# chaprshield.net
KiCad netlist of a schematic drawn in EAGLE
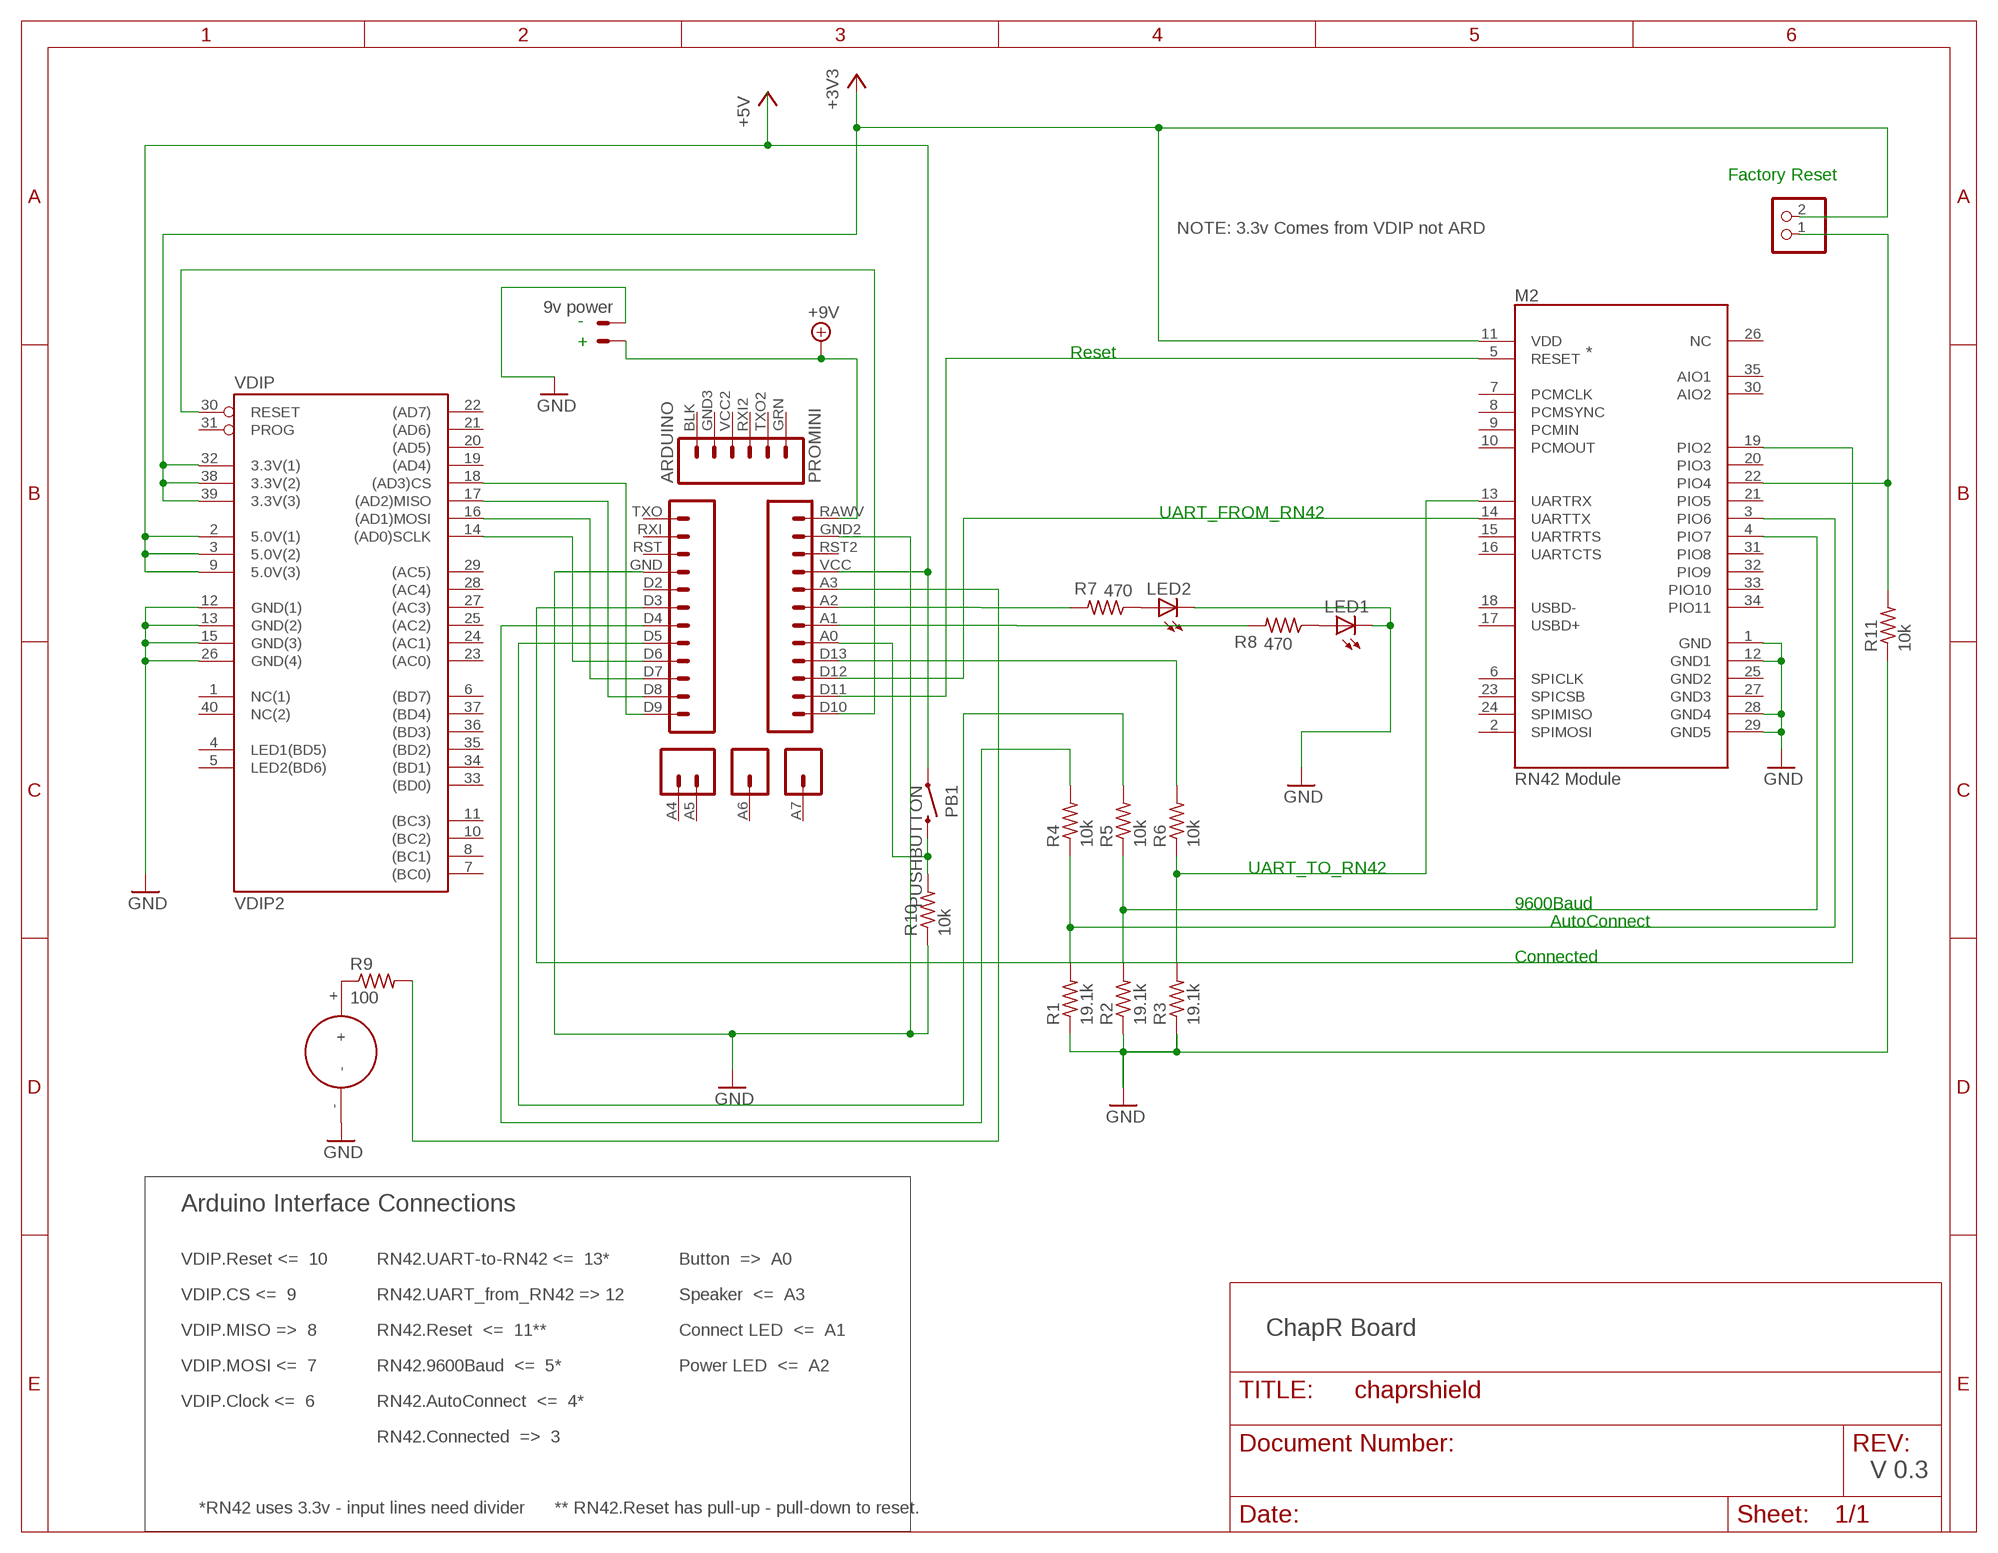
[diagram p0: schematic, sheet 1]

(export (version "E")
  (design (tool "Eeschema 10.0.6"))
  (components
    (comp (ref "-")
      (value "9v power")
      (footprint "eagle-import:22-23-2021")
      (fields (field (name "MF") "MOLEX") (field (name "MPN") "22-23-2021"))
      (libsource (lib "eagle-import") (part "22-23-2021"))
    )
    (comp (ref "ARDUINO")
      (value "PROMINI")
      (footprint "eagle-import:PROMINI")
      (libsource (lib "eagle-import") (part "PROMINI"))
    )
    (comp (ref "JP1")
      (value "PINHD-1X2")
      (footprint "eagle-import:1X02")
      (libsource (lib "eagle-import") (part "PINHD-1X2"))
    )
    (comp (ref "LED1")
      (value "LED3MM")
      (footprint "eagle-import:LED3MM")
      (libsource (lib "eagle-import") (part "LED3MM"))
    )
    (comp (ref "LED2")
      (value "LED3MM")
      (footprint "eagle-import:LED3MM")
      (libsource (lib "eagle-import") (part "LED3MM"))
    )
    (comp (ref "M2")
      (value "RN42 Module")
      (footprint "eagle-import:RN41")
      (libsource (lib "eagle-import") (part "BLUETOOTH-RN41{dblquote}"))
    )
    (comp (ref "PB1")
      (value "PUSHBUTTON")
      (footprint "eagle-import:2-PIN-PUSHBUTTON")
      (libsource (lib "eagle-import") (part "PUSHBUTTON"))
    )
    (comp (ref "R1")
      (value "19.1k")
      (footprint "eagle-import:0207_10")
      (libsource (lib "eagle-import") (part "R-US_0207/10"))
    )
    (comp (ref "R2")
      (value "19.1k")
      (footprint "eagle-import:0207_10")
      (libsource (lib "eagle-import") (part "R-US_0207/10"))
    )
    (comp (ref "R3")
      (value "19.1k")
      (footprint "eagle-import:0207_10")
      (libsource (lib "eagle-import") (part "R-US_0207/10"))
    )
    (comp (ref "R4")
      (value "10k")
      (footprint "eagle-import:0207_10")
      (libsource (lib "eagle-import") (part "R-US_0207/10"))
    )
    (comp (ref "R5")
      (value "10k")
      (footprint "eagle-import:0207_10")
      (libsource (lib "eagle-import") (part "R-US_0207/10"))
    )
    (comp (ref "R6")
      (value "10k")
      (footprint "eagle-import:0207_10")
      (libsource (lib "eagle-import") (part "R-US_0207/10"))
    )
    (comp (ref "R7")
      (value "470")
      (footprint "eagle-import:0207_10")
      (libsource (lib "eagle-import") (part "R-US_0207/10"))
    )
    (comp (ref "R8")
      (value "470")
      (footprint "eagle-import:0207_10")
      (libsource (lib "eagle-import") (part "R-US_0207/10"))
    )
    (comp (ref "R9")
      (value "100")
      (footprint "eagle-import:0207_10")
      (libsource (lib "eagle-import") (part "R-US_0207/10"))
    )
    (comp (ref "R10")
      (value "10k")
      (footprint "eagle-import:0207_10")
      (libsource (lib "eagle-import") (part "R-US_0207/10"))
    )
    (comp (ref "R11")
      (value "10k")
      (footprint "eagle-import:0207_10")
      (libsource (lib "eagle-import") (part "R-US_0207/10"))
    )
    (comp (ref "U$2")
      (value "SPEAKER")
      (footprint "eagle-import:SPEAKER")
      (libsource (lib "eagle-import") (part "SPEAKER"))
    )
    (comp (ref "VDIP")
      (value "VDIP2")
      (footprint "eagle-import:VDIP2")
      (libsource (lib "eagle-import") (part "VDIP2"))
    )
  )
  (nets
    (net (code "1") (name "+3V3") (class "Default")
      (node (ref "JP1") (pin "2") (pinfunction "2_2") (pintype "passive"))
      (node (ref "M2") (pin "11") (pinfunction "VDD_11") (pintype "bidirectional"))
      (node (ref "VDIP") (pin "32") (pinfunction "3.3V(1)_32") (pintype "input"))
      (node (ref "VDIP") (pin "38") (pinfunction "3.3V(2)_38") (pintype "power_in"))
      (node (ref "VDIP") (pin "39") (pinfunction "3.3V(3)_39") (pintype "input"))
    )
    (net (code "3") (name "+9V") (class "Default")
      (node (ref "-") (pin "2") (pinfunction "S_2") (pintype "passive"))
      (node (ref "ARDUINO") (pin "RAWV") (pinfunction "RAWV_RAWV") (pintype "passive"))
    )
    (net (code "4") (name "/LED1(BD5)") (class "Default")
      (node (ref "VDIP") (pin "4") (pinfunction "LED1(BD5)_4") (pintype "power_in"))
    )
    (net (code "5") (name "/LED2(BD6)") (class "Default")
      (node (ref "VDIP") (pin "5") (pinfunction "LED2(BD6)_5") (pintype "power_in"))
    )
    (net (code "6") (name "/NC(1)") (class "Default")
      (node (ref "VDIP") (pin "1") (pinfunction "NC(1)_1") (pintype "power_in"))
    )
    (net (code "7") (name "/NC(2)") (class "Default")
      (node (ref "VDIP") (pin "40") (pinfunction "NC(2)_40") (pintype "power_in"))
    )
    (net (code "8") (name "GND") (class "Default")
      (node (ref "-") (pin "1") (pinfunction "S_1") (pintype "passive"))
      (node (ref "ARDUINO") (pin "GND") (pinfunction "GND_GND") (pintype "passive"))
      (node (ref "ARDUINO") (pin "GND2") (pinfunction "GND2_GND2") (pintype "passive"))
      (node (ref "LED1") (pin "K") (pinfunction "C_K") (pintype "passive"))
      (node (ref "LED2") (pin "K") (pinfunction "C_K") (pintype "passive"))
      (node (ref "M2") (pin "1") (pinfunction "GND_1") (pintype "bidirectional"))
      (node (ref "M2") (pin "12") (pinfunction "GND1_12") (pintype "bidirectional"))
      (node (ref "M2") (pin "28") (pinfunction "GND4_28") (pintype "bidirectional"))
      (node (ref "M2") (pin "29") (pinfunction "GND5_29") (pintype "bidirectional"))
      (node (ref "R1") (pin "1") (pinfunction "1_1") (pintype "passive"))
      (node (ref "R10") (pin "1") (pinfunction "1_1") (pintype "passive"))
      (node (ref "R11") (pin "1") (pinfunction "1_1") (pintype "passive"))
      (node (ref "R2") (pin "1") (pinfunction "1_1") (pintype "passive"))
      (node (ref "R3") (pin "1") (pinfunction "1_1") (pintype "passive"))
      (node (ref "U$2") (pin "-") (pinfunction "-_-") (pintype "bidirectional"))
      (node (ref "VDIP") (pin "12") (pinfunction "GND(1)_12") (pintype "power_in"))
      (node (ref "VDIP") (pin "13") (pinfunction "GND(2)_13") (pintype "power_in"))
      (node (ref "VDIP") (pin "15") (pinfunction "GND(3)_15") (pintype "power_in"))
      (node (ref "VDIP") (pin "26") (pinfunction "GND(4)_26") (pintype "power_in"))
    )
    (net (code "9") (name "Net-(ARDUINO-PadA1)") (class "Default")
      (node (ref "ARDUINO") (pin "A1") (pinfunction "A1_A1") (pintype "passive"))
      (node (ref "R8") (pin "2") (pinfunction "2_2") (pintype "passive"))
    )
    (net (code "10") (name "Net-(ARDUINO-PadA2)") (class "Default")
      (node (ref "ARDUINO") (pin "A2") (pinfunction "A2_A2") (pintype "passive"))
      (node (ref "R7") (pin "2") (pinfunction "2_2") (pintype "passive"))
    )
    (net (code "11") (name "Net-(ARDUINO-PadA3)") (class "Default")
      (node (ref "ARDUINO") (pin "A3") (pinfunction "A3_A3") (pintype "passive"))
      (node (ref "R9") (pin "2") (pinfunction "2_2") (pintype "passive"))
    )
    (net (code "12") (name "Net-(ARDUINO-PadD4)") (class "Default")
      (node (ref "ARDUINO") (pin "D4") (pinfunction "D4_D4") (pintype "passive"))
      (node (ref "R4") (pin "2") (pinfunction "2_2") (pintype "passive"))
    )
    (net (code "13") (name "Net-(ARDUINO-PadD5)") (class "Default")
      (node (ref "ARDUINO") (pin "D5") (pinfunction "D5_D5") (pintype "passive"))
      (node (ref "R5") (pin "2") (pinfunction "2_2") (pintype "passive"))
    )
    (net (code "14") (name "Net-(ARDUINO-PadD13)") (class "Default")
      (node (ref "ARDUINO") (pin "D13") (pinfunction "D13_D13") (pintype "passive"))
      (node (ref "R6") (pin "2") (pinfunction "2_2") (pintype "passive"))
    )
    (net (code "15") (name "Net-(LED1-PadA)") (class "Default")
      (node (ref "LED1") (pin "A") (pinfunction "A_A") (pintype "passive"))
      (node (ref "R8") (pin "1") (pinfunction "1_1") (pintype "passive"))
    )
    (net (code "16") (name "Net-(LED2-PadA)") (class "Default")
      (node (ref "LED2") (pin "A") (pinfunction "A_A") (pintype "passive"))
      (node (ref "R7") (pin "1") (pinfunction "1_1") (pintype "passive"))
    )
    (net (code "17") (name "Net-(M2-PIO2)") (class "Default")
      (node (ref "ARDUINO") (pin "D3") (pinfunction "D3_D3") (pintype "passive"))
      (node (ref "M2") (pin "19") (pinfunction "PIO2_19") (pintype "bidirectional"))
    )
    (net (code "18") (name "Net-(M2-PIO4)") (class "Default")
      (node (ref "JP1") (pin "1") (pinfunction "1_1") (pintype "passive"))
      (node (ref "M2") (pin "22") (pinfunction "PIO4_22") (pintype "bidirectional"))
      (node (ref "R11") (pin "2") (pinfunction "2_2") (pintype "passive"))
    )
    (net (code "19") (name "Net-(M2-PIO6)") (class "Default")
      (node (ref "M2") (pin "3") (pinfunction "PIO6_3") (pintype "bidirectional"))
      (node (ref "R1") (pin "2") (pinfunction "2_2") (pintype "passive"))
      (node (ref "R4") (pin "1") (pinfunction "1_1") (pintype "passive"))
    )
    (net (code "20") (name "Net-(M2-PIO7)") (class "Default")
      (node (ref "M2") (pin "4") (pinfunction "PIO7_4") (pintype "bidirectional"))
      (node (ref "R2") (pin "2") (pinfunction "2_2") (pintype "passive"))
      (node (ref "R5") (pin "1") (pinfunction "1_1") (pintype "passive"))
    )
    (net (code "21") (name "Net-(M2-RESET)") (class "Default")
      (node (ref "ARDUINO") (pin "D11") (pinfunction "D11_D11") (pintype "passive"))
      (node (ref "M2") (pin "5") (pinfunction "RESET_5") (pintype "bidirectional"))
    )
    (net (code "22") (name "Net-(M2-UARTRX)") (class "Default")
      (node (ref "M2") (pin "13") (pinfunction "UARTRX_13") (pintype "bidirectional"))
      (node (ref "R3") (pin "2") (pinfunction "2_2") (pintype "passive"))
      (node (ref "R6") (pin "1") (pinfunction "1_1") (pintype "passive"))
    )
    (net (code "23") (name "Net-(M2-UARTTX)") (class "Default")
      (node (ref "ARDUINO") (pin "D12") (pinfunction "D12_D12") (pintype "passive"))
      (node (ref "M2") (pin "14") (pinfunction "UARTTX_14") (pintype "bidirectional"))
    )
    (net (code "24") (name "Net-(PB1-1)") (class "Default")
      (node (ref "ARDUINO") (pin "VCC") (pinfunction "VCC_VCC") (pintype "passive"))
      (node (ref "PB1") (pin "P$1") (pinfunction "1_P$1") (pintype "passive"))
      (node (ref "VDIP") (pin "2") (pinfunction "5.0V(1)_2") (pintype "power_in"))
      (node (ref "VDIP") (pin "3") (pinfunction "5.0V(2)_3") (pintype "power_in"))
      (node (ref "VDIP") (pin "9") (pinfunction "5.0V(3)_9") (pintype "power_in"))
    )
    (net (code "25") (name "Net-(PB1-2)") (class "Default")
      (node (ref "ARDUINO") (pin "A0") (pinfunction "A0_A0") (pintype "passive"))
      (node (ref "PB1") (pin "P$2") (pinfunction "2_P$2") (pintype "passive"))
      (node (ref "R10") (pin "2") (pinfunction "2_2") (pintype "passive"))
    )
    (net (code "26") (name "Net-(R9-Pad1)") (class "Default")
      (node (ref "R9") (pin "1") (pinfunction "1_1") (pintype "passive"))
      (node (ref "U$2") (pin "+") (pinfunction "+_+") (pintype "bidirectional"))
    )
    (net (code "27") (name "Net-(VDIP-(AD0)SCLK)") (class "Default")
      (node (ref "ARDUINO") (pin "D6") (pinfunction "D6_D6") (pintype "passive"))
      (node (ref "VDIP") (pin "14") (pinfunction "(AD0)SCLK_14") (pintype "bidirectional"))
    )
    (net (code "28") (name "Net-(VDIP-(AD1)MOSI)") (class "Default")
      (node (ref "ARDUINO") (pin "D7") (pinfunction "D7_D7") (pintype "passive"))
      (node (ref "VDIP") (pin "16") (pinfunction "(AD1)MOSI_16") (pintype "bidirectional"))
    )
    (net (code "29") (name "Net-(VDIP-(AD2)MISO)") (class "Default")
      (node (ref "ARDUINO") (pin "D8") (pinfunction "D8_D8") (pintype "passive"))
      (node (ref "VDIP") (pin "17") (pinfunction "(AD2)MISO_17") (pintype "bidirectional"))
    )
    (net (code "30") (name "Net-(VDIP-(AD3)CS)") (class "Default")
      (node (ref "ARDUINO") (pin "D9") (pinfunction "D9_D9") (pintype "passive"))
      (node (ref "VDIP") (pin "18") (pinfunction "(AD3)CS_18") (pintype "bidirectional"))
    )
    (net (code "31") (name "Net-(VDIP-RESET)") (class "Default")
      (node (ref "ARDUINO") (pin "D10") (pinfunction "D10_D10") (pintype "passive"))
      (node (ref "VDIP") (pin "30") (pinfunction "RESET_30") (pintype "input"))
    )
    (net (code "32") (name "unconnected-(ARDUINO-PadA4)") (class "Default")
      (node (ref "ARDUINO") (pin "A4") (pinfunction "A4_A4") (pintype "passive"))
    )
    (net (code "33") (name "unconnected-(ARDUINO-PadA5)") (class "Default")
      (node (ref "ARDUINO") (pin "A5") (pinfunction "A5_A5") (pintype "passive"))
    )
    (net (code "34") (name "unconnected-(ARDUINO-PadA6)") (class "Default")
      (node (ref "ARDUINO") (pin "A6") (pinfunction "A6_A6") (pintype "passive"))
    )
    (net (code "35") (name "unconnected-(ARDUINO-PadA7)") (class "Default")
      (node (ref "ARDUINO") (pin "A7") (pinfunction "A7_A7") (pintype "passive"))
    )
    (net (code "36") (name "unconnected-(ARDUINO-PadBLK)") (class "Default")
      (node (ref "ARDUINO") (pin "BLK") (pinfunction "BLK_BLK") (pintype "passive"))
    )
    (net (code "37") (name "unconnected-(ARDUINO-PadD2)") (class "Default")
      (node (ref "ARDUINO") (pin "D2") (pinfunction "D2_D2") (pintype "passive"))
    )
    (net (code "38") (name "unconnected-(ARDUINO-PadGND3)") (class "Default")
      (node (ref "ARDUINO") (pin "GND3") (pinfunction "GND3_GND3") (pintype "passive"))
    )
    (net (code "39") (name "unconnected-(ARDUINO-PadGRN)") (class "Default")
      (node (ref "ARDUINO") (pin "GRN") (pinfunction "GRN_GRN") (pintype "passive"))
    )
    (net (code "40") (name "unconnected-(ARDUINO-PadRST)") (class "Default")
      (node (ref "ARDUINO") (pin "RST") (pinfunction "RST_RST") (pintype "passive"))
    )
    (net (code "41") (name "unconnected-(ARDUINO-PadRST2)") (class "Default")
      (node (ref "ARDUINO") (pin "RST2") (pinfunction "RST2_RST2") (pintype "passive"))
    )
    (net (code "42") (name "unconnected-(ARDUINO-PadRXI)") (class "Default")
      (node (ref "ARDUINO") (pin "RXI") (pinfunction "RXI_RXI") (pintype "passive"))
    )
    (net (code "43") (name "unconnected-(ARDUINO-PadRXI2)") (class "Default")
      (node (ref "ARDUINO") (pin "RXI2") (pinfunction "RXI2_RXI2") (pintype "passive"))
    )
    (net (code "44") (name "unconnected-(ARDUINO-PadTXO)") (class "Default")
      (node (ref "ARDUINO") (pin "TXO") (pinfunction "TXO_TXO") (pintype "passive"))
    )
    (net (code "45") (name "unconnected-(ARDUINO-PadTXO2)") (class "Default")
      (node (ref "ARDUINO") (pin "TXO2") (pinfunction "TXO2_TXO2") (pintype "passive"))
    )
    (net (code "46") (name "unconnected-(ARDUINO-PadVCC2)") (class "Default")
      (node (ref "ARDUINO") (pin "VCC2") (pinfunction "VCC2_VCC2") (pintype "passive"))
    )
    (net (code "47") (name "unconnected-(M2-AIO1-Pad35)") (class "Default")
      (node (ref "M2") (pin "35") (pinfunction "AIO1_35") (pintype "bidirectional"))
    )
    (net (code "48") (name "unconnected-(M2-AIO2-Pad30)") (class "Default")
      (node (ref "M2") (pin "30") (pinfunction "AIO2_30") (pintype "bidirectional"))
    )
    (net (code "49") (name "unconnected-(M2-GND2-Pad25)") (class "Default")
      (node (ref "M2") (pin "25") (pinfunction "GND2_25") (pintype "bidirectional"))
    )
    (net (code "50") (name "unconnected-(M2-GND3-Pad27)") (class "Default")
      (node (ref "M2") (pin "27") (pinfunction "GND3_27") (pintype "bidirectional"))
    )
    (net (code "51") (name "unconnected-(M2-NC-Pad26)") (class "Default")
      (node (ref "M2") (pin "26") (pinfunction "NC_26") (pintype "bidirectional"))
    )
    (net (code "52") (name "unconnected-(M2-PCMCLK-Pad7)") (class "Default")
      (node (ref "M2") (pin "7") (pinfunction "PCMCLK_7") (pintype "bidirectional"))
    )
    (net (code "53") (name "unconnected-(M2-PCMIN-Pad9)") (class "Default")
      (node (ref "M2") (pin "9") (pinfunction "PCMIN_9") (pintype "bidirectional"))
    )
    (net (code "54") (name "unconnected-(M2-PCMOUT-Pad10)") (class "Default")
      (node (ref "M2") (pin "10") (pinfunction "PCMOUT_10") (pintype "bidirectional"))
    )
    (net (code "55") (name "unconnected-(M2-PCMSYNC-Pad8)") (class "Default")
      (node (ref "M2") (pin "8") (pinfunction "PCMSYNC_8") (pintype "bidirectional"))
    )
    (net (code "56") (name "unconnected-(M2-PIO3-Pad20)") (class "Default")
      (node (ref "M2") (pin "20") (pinfunction "PIO3_20") (pintype "bidirectional"))
    )
    (net (code "57") (name "unconnected-(M2-PIO5-Pad21)") (class "Default")
      (node (ref "M2") (pin "21") (pinfunction "PIO5_21") (pintype "bidirectional"))
    )
    (net (code "58") (name "unconnected-(M2-PIO8-Pad31)") (class "Default")
      (node (ref "M2") (pin "31") (pinfunction "PIO8_31") (pintype "bidirectional"))
    )
    (net (code "59") (name "unconnected-(M2-PIO9-Pad32)") (class "Default")
      (node (ref "M2") (pin "32") (pinfunction "PIO9_32") (pintype "bidirectional"))
    )
    (net (code "60") (name "unconnected-(M2-PIO10-Pad33)") (class "Default")
      (node (ref "M2") (pin "33") (pinfunction "PIO10_33") (pintype "bidirectional"))
    )
    (net (code "61") (name "unconnected-(M2-PIO11-Pad34)") (class "Default")
      (node (ref "M2") (pin "34") (pinfunction "PIO11_34") (pintype "bidirectional"))
    )
    (net (code "62") (name "unconnected-(M2-SPICLK-Pad6)") (class "Default")
      (node (ref "M2") (pin "6") (pinfunction "SPICLK_6") (pintype "bidirectional"))
    )
    (net (code "63") (name "unconnected-(M2-SPICSB-Pad23)") (class "Default")
      (node (ref "M2") (pin "23") (pinfunction "SPICSB_23") (pintype "bidirectional"))
    )
    (net (code "64") (name "unconnected-(M2-SPIMISO-Pad24)") (class "Default")
      (node (ref "M2") (pin "24") (pinfunction "SPIMISO_24") (pintype "bidirectional"))
    )
    (net (code "65") (name "unconnected-(M2-SPIMOSI-Pad2)") (class "Default")
      (node (ref "M2") (pin "2") (pinfunction "SPIMOSI_2") (pintype "bidirectional"))
    )
    (net (code "66") (name "unconnected-(M2-UARTCTS-Pad16)") (class "Default")
      (node (ref "M2") (pin "16") (pinfunction "UARTCTS_16") (pintype "bidirectional"))
    )
    (net (code "67") (name "unconnected-(M2-UARTRTS-Pad15)") (class "Default")
      (node (ref "M2") (pin "15") (pinfunction "UARTRTS_15") (pintype "bidirectional"))
    )
    (net (code "68") (name "unconnected-(M2-USBD+-Pad17)") (class "Default")
      (node (ref "M2") (pin "17") (pinfunction "USBD+_17") (pintype "bidirectional"))
    )
    (net (code "69") (name "unconnected-(M2-USBD--Pad18)") (class "Default")
      (node (ref "M2") (pin "18") (pinfunction "USBD-_18") (pintype "bidirectional"))
    )
    (net (code "70") (name "unconnected-(VDIP-(AC0)-Pad23)") (class "Default")
      (node (ref "VDIP") (pin "23") (pinfunction "(AC0)_23") (pintype "bidirectional"))
    )
    (net (code "71") (name "unconnected-(VDIP-(AC1)-Pad24)") (class "Default")
      (node (ref "VDIP") (pin "24") (pinfunction "(AC1)_24") (pintype "bidirectional"))
    )
    (net (code "72") (name "unconnected-(VDIP-(AC2)-Pad25)") (class "Default")
      (node (ref "VDIP") (pin "25") (pinfunction "(AC2)_25") (pintype "bidirectional"))
    )
    (net (code "73") (name "unconnected-(VDIP-(AC3)-Pad27)") (class "Default")
      (node (ref "VDIP") (pin "27") (pinfunction "(AC3)_27") (pintype "bidirectional"))
    )
    (net (code "74") (name "unconnected-(VDIP-(AC4)-Pad28)") (class "Default")
      (node (ref "VDIP") (pin "28") (pinfunction "(AC4)_28") (pintype "bidirectional"))
    )
    (net (code "75") (name "unconnected-(VDIP-(AC5)-Pad29)") (class "Default")
      (node (ref "VDIP") (pin "29") (pinfunction "(AC5)_29") (pintype "bidirectional"))
    )
    (net (code "76") (name "unconnected-(VDIP-(AD4)-Pad19)") (class "Default")
      (node (ref "VDIP") (pin "19") (pinfunction "(AD4)_19") (pintype "bidirectional"))
    )
    (net (code "77") (name "unconnected-(VDIP-(AD5)-Pad20)") (class "Default")
      (node (ref "VDIP") (pin "20") (pinfunction "(AD5)_20") (pintype "bidirectional"))
    )
    (net (code "78") (name "unconnected-(VDIP-(AD6)-Pad21)") (class "Default")
      (node (ref "VDIP") (pin "21") (pinfunction "(AD6)_21") (pintype "bidirectional"))
    )
    (net (code "79") (name "unconnected-(VDIP-(AD7)-Pad22)") (class "Default")
      (node (ref "VDIP") (pin "22") (pinfunction "(AD7)_22") (pintype "bidirectional"))
    )
    (net (code "80") (name "unconnected-(VDIP-(BC0)-Pad7)") (class "Default")
      (node (ref "VDIP") (pin "7") (pinfunction "(BC0)_7") (pintype "bidirectional"))
    )
    (net (code "81") (name "unconnected-(VDIP-(BC1)-Pad8)") (class "Default")
      (node (ref "VDIP") (pin "8") (pinfunction "(BC1)_8") (pintype "bidirectional"))
    )
    (net (code "82") (name "unconnected-(VDIP-(BC2)-Pad10)") (class "Default")
      (node (ref "VDIP") (pin "10") (pinfunction "(BC2)_10") (pintype "bidirectional"))
    )
    (net (code "83") (name "unconnected-(VDIP-(BC3)-Pad11)") (class "Default")
      (node (ref "VDIP") (pin "11") (pinfunction "(BC3)_11") (pintype "bidirectional"))
    )
    (net (code "84") (name "unconnected-(VDIP-(BD0)-Pad33)") (class "Default")
      (node (ref "VDIP") (pin "33") (pinfunction "(BD0)_33") (pintype "bidirectional"))
    )
    (net (code "85") (name "unconnected-(VDIP-(BD1)-Pad34)") (class "Default")
      (node (ref "VDIP") (pin "34") (pinfunction "(BD1)_34") (pintype "bidirectional"))
    )
    (net (code "86") (name "unconnected-(VDIP-(BD2)-Pad35)") (class "Default")
      (node (ref "VDIP") (pin "35") (pinfunction "(BD2)_35") (pintype "bidirectional"))
    )
    (net (code "87") (name "unconnected-(VDIP-(BD3)-Pad36)") (class "Default")
      (node (ref "VDIP") (pin "36") (pinfunction "(BD3)_36") (pintype "bidirectional"))
    )
    (net (code "88") (name "unconnected-(VDIP-(BD4)-Pad37)") (class "Default")
      (node (ref "VDIP") (pin "37") (pinfunction "(BD4)_37") (pintype "bidirectional"))
    )
    (net (code "89") (name "unconnected-(VDIP-(BD7)-Pad6)") (class "Default")
      (node (ref "VDIP") (pin "6") (pinfunction "(BD7)_6") (pintype "bidirectional"))
    )
    (net (code "90") (name "unconnected-(VDIP-PROG-Pad31)") (class "Default")
      (node (ref "VDIP") (pin "31") (pinfunction "PROG_31") (pintype "input"))
    )
  )
)
